# Adafruit_Feather_M0_Basic_rev_C.net
KiCad netlist of a schematic drawn in EAGLE
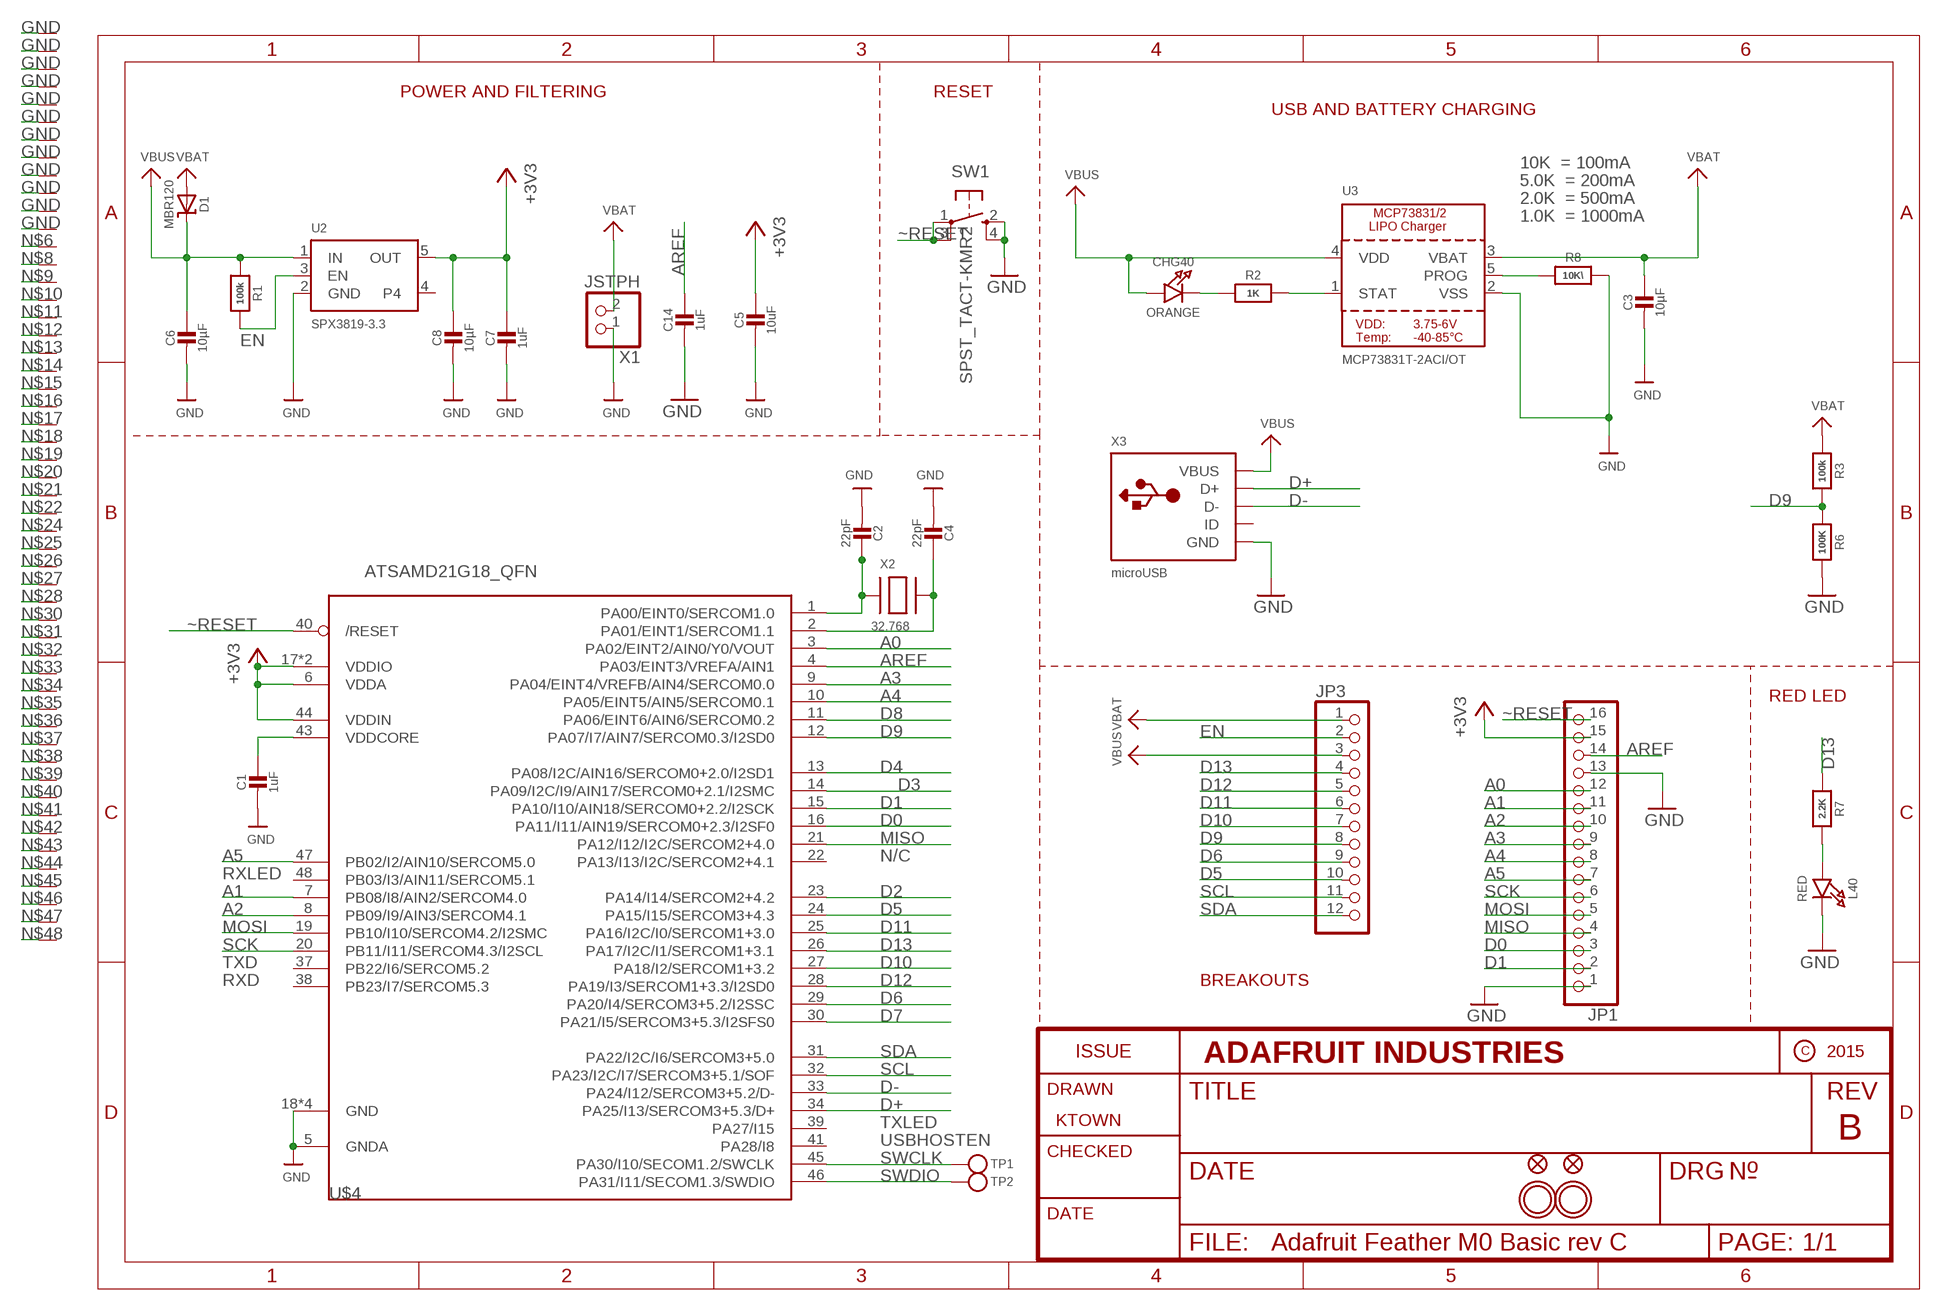
[diagram p0: schematic, sheet 1]

(export (version "E")
  (design (tool "Eeschema 10.0.6"))
  (components
    (comp (ref "C1")
      (value "1uF")
      (footprint "eagle-import:0603-NO")
      (libsource (lib "eagle-import") (part "CAP_CERAMIC0603_NO"))
    )
    (comp (ref "C2")
      (value "22pF")
      (footprint "eagle-import:0603-NO")
      (libsource (lib "eagle-import") (part "CAP_CERAMIC0603_NO"))
    )
    (comp (ref "C3")
      (value "10µF")
      (footprint "eagle-import:0805-NO")
      (libsource (lib "eagle-import") (part "CAP_CERAMIC0805-NOOUTLINE"))
    )
    (comp (ref "C4")
      (value "22pF")
      (footprint "eagle-import:0603-NO")
      (libsource (lib "eagle-import") (part "CAP_CERAMIC0603_NO"))
    )
    (comp (ref "C5")
      (value "10uF")
      (footprint "eagle-import:0805-NO")
      (libsource (lib "eagle-import") (part "CAP_CERAMIC0805-NOOUTLINE"))
    )
    (comp (ref "C6")
      (value "10µF")
      (footprint "eagle-import:0805-NO")
      (libsource (lib "eagle-import") (part "CAP_CERAMIC0805-NOOUTLINE"))
    )
    (comp (ref "C7")
      (value "1uF")
      (footprint "eagle-import:0603-NO")
      (libsource (lib "eagle-import") (part "CAP_CERAMIC0603_NO"))
    )
    (comp (ref "C8")
      (value "10µF")
      (footprint "eagle-import:0805-NO")
      (libsource (lib "eagle-import") (part "CAP_CERAMIC0805-NOOUTLINE"))
    )
    (comp (ref "C14")
      (value "1uF")
      (footprint "eagle-import:0603-NO")
      (libsource (lib "eagle-import") (part "CAP_CERAMIC0603_NO"))
    )
    (comp (ref "CHG40")
      (value "ORANGE")
      (footprint "eagle-import:CHIPLED_0805_NOOUTLINE")
      (libsource (lib "eagle-import") (part "LED0805_NOOUTLINE"))
    )
    (comp (ref "D1")
      (value "MBR120")
      (footprint "eagle-import:SOD-123")
      (libsource (lib "eagle-import") (part "DIODE-SCHOTTKYSOD-123"))
    )
    (comp (ref "JP1")
      (value "HEADER-1X16ROUND")
      (footprint "eagle-import:1X16_ROUND")
      (libsource (lib "eagle-import") (part "HEADER-1X16ROUND"))
    )
    (comp (ref "JP3")
      (value "HEADER-1X12")
      (footprint "eagle-import:1X12_ROUND")
      (libsource (lib "eagle-import") (part "HEADER-1X12"))
    )
    (comp (ref "L40")
      (value "RED")
      (footprint "eagle-import:CHIPLED_0805_NOOUTLINE")
      (libsource (lib "eagle-import") (part "LED0805_NOOUTLINE"))
    )
    (comp (ref "R1")
      (value "100k")
      (footprint "eagle-import:0603-NO")
      (libsource (lib "eagle-import") (part "RESISTOR_0603_NOOUT"))
    )
    (comp (ref "R2")
      (value "1K")
      (footprint "eagle-import:0603-NO")
      (libsource (lib "eagle-import") (part "RESISTOR_0603_NOOUT"))
    )
    (comp (ref "R3")
      (value "100k")
      (footprint "eagle-import:0603-NO")
      (libsource (lib "eagle-import") (part "RESISTOR_0603_NOOUT"))
    )
    (comp (ref "R6")
      (value "100K")
      (footprint "eagle-import:0603-NO")
      (libsource (lib "eagle-import") (part "RESISTOR_0603_NOOUT"))
    )
    (comp (ref "R7")
      (value "2.2K")
      (footprint "eagle-import:0603-NO")
      (libsource (lib "eagle-import") (part "RESISTOR_0603_NOOUT"))
    )
    (comp (ref "R8")
      (value "10K\\")
      (footprint "eagle-import:0603-NO")
      (libsource (lib "eagle-import") (part "RESISTOR_0603_NOOUT"))
    )
    (comp (ref "SW1")
      (value "SPST_TACT-KMR2")
      (footprint "eagle-import:KMR2")
      (libsource (lib "eagle-import") (part "SPST_TACT-KMR2"))
    )
    (comp (ref "TP1")
      (value "TESTPOINTROUND1.5MM")
      (footprint "eagle-import:TESTPOINT_ROUND_1.5MM")
      (libsource (lib "eagle-import") (part "TESTPOINTROUND1.5MM"))
    )
    (comp (ref "TP2")
      (value "TESTPOINTROUND1.5MM")
      (footprint "eagle-import:TESTPOINT_ROUND_1.5MM")
      (libsource (lib "eagle-import") (part "TESTPOINTROUND1.5MM"))
    )
    (comp (ref "U$4")
      (value "ATSAMD21G18_QFN")
      (footprint "eagle-import:TQFN48_7MM")
      (libsource (lib "eagle-import") (part "ATSAMD21J_QFN"))
    )
    (comp (ref "U$31")
      (value "MOUNTINGHOLE2.5")
      (footprint "eagle-import:MOUNTINGHOLE_2.5_PLATED")
      (libsource (lib "eagle-import") (part "MOUNTINGHOLE2.5"))
    )
    (comp (ref "U$32")
      (value "MOUNTINGHOLE2.5")
      (footprint "eagle-import:MOUNTINGHOLE_2.5_PLATED")
      (libsource (lib "eagle-import") (part "MOUNTINGHOLE2.5"))
    )
    (comp (ref "U$34")
      (value "FIDUCIAL\"\"")
      (footprint "eagle-import:FIDUCIAL_1MM")
      (libsource (lib "eagle-import") (part "FIDUCIAL{dblquote}{dblquote}"))
    )
    (comp (ref "U$35")
      (value "FIDUCIAL\"\"")
      (footprint "eagle-import:FIDUCIAL_1MM")
      (libsource (lib "eagle-import") (part "FIDUCIAL{dblquote}{dblquote}"))
    )
    (comp (ref "U2")
      (value "SPX3819-3.3")
      (footprint "eagle-import:SOT23-5")
      (libsource (lib "eagle-import") (part "VREG_SOT23-5"))
    )
    (comp (ref "U3")
      (value "MCP73831T-2ACI/OT")
      (footprint "eagle-import:SOT23-5")
      (libsource (lib "eagle-import") (part "MCP73831/2"))
    )
    (comp (ref "VP_0")
      (value "VPDEV0")
      (footprint "eagle-import:VPAC0")
      (libsource (lib "eagle-import") (part "VPDEV0"))
    )
    (comp (ref "VP_1")
      (value "VPDEV0")
      (footprint "eagle-import:VPAC0")
      (libsource (lib "eagle-import") (part "VPDEV0"))
    )
    (comp (ref "VP_2")
      (value "VPDEV0")
      (footprint "eagle-import:VPAC0")
      (libsource (lib "eagle-import") (part "VPDEV0"))
    )
    (comp (ref "VP_3")
      (value "VPDEV0")
      (footprint "eagle-import:VPAC0")
      (libsource (lib "eagle-import") (part "VPDEV0"))
    )
    (comp (ref "VP_4")
      (value "VPDEV0")
      (footprint "eagle-import:VPAC0")
      (libsource (lib "eagle-import") (part "VPDEV0"))
    )
    (comp (ref "VP_5")
      (value "VPDEV0")
      (footprint "eagle-import:VPAC0")
      (libsource (lib "eagle-import") (part "VPDEV0"))
    )
    (comp (ref "VP_6")
      (value "VPDEV0")
      (footprint "eagle-import:VPAC0")
      (libsource (lib "eagle-import") (part "VPDEV0"))
    )
    (comp (ref "VP_7")
      (value "VPDEV0")
      (footprint "eagle-import:VPAC0")
      (libsource (lib "eagle-import") (part "VPDEV0"))
    )
    (comp (ref "VP_8")
      (value "VPDEV0")
      (footprint "eagle-import:VPAC0")
      (libsource (lib "eagle-import") (part "VPDEV0"))
    )
    (comp (ref "VP_9")
      (value "VPDEV0")
      (footprint "eagle-import:VPAC0")
      (libsource (lib "eagle-import") (part "VPDEV0"))
    )
    (comp (ref "VP_10")
      (value "VPDEV0")
      (footprint "eagle-import:VPAC0")
      (libsource (lib "eagle-import") (part "VPDEV0"))
    )
    (comp (ref "VP_11")
      (value "VPDEV0")
      (footprint "eagle-import:VPAC0")
      (libsource (lib "eagle-import") (part "VPDEV0"))
    )
    (comp (ref "VP_12")
      (value "VPDEV1")
      (footprint "eagle-import:VPAC1")
      (libsource (lib "eagle-import") (part "VPDEV1"))
    )
    (comp (ref "VP_13")
      (value "VPDEV1")
      (footprint "eagle-import:VPAC1")
      (libsource (lib "eagle-import") (part "VPDEV1"))
    )
    (comp (ref "VP_14")
      (value "VPDEV1")
      (footprint "eagle-import:VPAC1")
      (libsource (lib "eagle-import") (part "VPDEV1"))
    )
    (comp (ref "VP_15")
      (value "VPDEV1")
      (footprint "eagle-import:VPAC1")
      (libsource (lib "eagle-import") (part "VPDEV1"))
    )
    (comp (ref "VP_16")
      (value "VPDEV1")
      (footprint "eagle-import:VPAC1")
      (libsource (lib "eagle-import") (part "VPDEV1"))
    )
    (comp (ref "VP_17")
      (value "VPDEV1")
      (footprint "eagle-import:VPAC1")
      (libsource (lib "eagle-import") (part "VPDEV1"))
    )
    (comp (ref "VP_18")
      (value "VPDEV1")
      (footprint "eagle-import:VPAC1")
      (libsource (lib "eagle-import") (part "VPDEV1"))
    )
    (comp (ref "VP_19")
      (value "VPDEV1")
      (footprint "eagle-import:VPAC1")
      (libsource (lib "eagle-import") (part "VPDEV1"))
    )
    (comp (ref "VP_20")
      (value "VPDEV1")
      (footprint "eagle-import:VPAC1")
      (libsource (lib "eagle-import") (part "VPDEV1"))
    )
    (comp (ref "VP_21")
      (value "VPDEV1")
      (footprint "eagle-import:VPAC1")
      (libsource (lib "eagle-import") (part "VPDEV1"))
    )
    (comp (ref "VP_22")
      (value "VPDEV1")
      (footprint "eagle-import:VPAC1")
      (libsource (lib "eagle-import") (part "VPDEV1"))
    )
    (comp (ref "VP_23")
      (value "VPDEV1")
      (footprint "eagle-import:VPAC1")
      (libsource (lib "eagle-import") (part "VPDEV1"))
    )
    (comp (ref "VP_24")
      (value "VPDEV1")
      (footprint "eagle-import:VPAC1")
      (libsource (lib "eagle-import") (part "VPDEV1"))
    )
    (comp (ref "VP_25")
      (value "VPDEV1")
      (footprint "eagle-import:VPAC1")
      (libsource (lib "eagle-import") (part "VPDEV1"))
    )
    (comp (ref "VP_26")
      (value "VPDEV1")
      (footprint "eagle-import:VPAC1")
      (libsource (lib "eagle-import") (part "VPDEV1"))
    )
    (comp (ref "VP_27")
      (value "VPDEV1")
      (footprint "eagle-import:VPAC1")
      (libsource (lib "eagle-import") (part "VPDEV1"))
    )
    (comp (ref "VP_28")
      (value "VPDEV1")
      (footprint "eagle-import:VPAC1")
      (libsource (lib "eagle-import") (part "VPDEV1"))
    )
    (comp (ref "VP_29")
      (value "VPDEV1")
      (footprint "eagle-import:VPAC1")
      (libsource (lib "eagle-import") (part "VPDEV1"))
    )
    (comp (ref "VP_30")
      (value "VPDEV1")
      (footprint "eagle-import:VPAC1")
      (libsource (lib "eagle-import") (part "VPDEV1"))
    )
    (comp (ref "VP_31")
      (value "VPDEV1")
      (footprint "eagle-import:VPAC1")
      (libsource (lib "eagle-import") (part "VPDEV1"))
    )
    (comp (ref "VP_32")
      (value "VPDEV1")
      (footprint "eagle-import:VPAC1")
      (libsource (lib "eagle-import") (part "VPDEV1"))
    )
    (comp (ref "VP_33")
      (value "VPDEV1")
      (footprint "eagle-import:VPAC1")
      (libsource (lib "eagle-import") (part "VPDEV1"))
    )
    (comp (ref "VP_34")
      (value "VPDEV1")
      (footprint "eagle-import:VPAC1")
      (libsource (lib "eagle-import") (part "VPDEV1"))
    )
    (comp (ref "VP_35")
      (value "VPDEV1")
      (footprint "eagle-import:VPAC1")
      (libsource (lib "eagle-import") (part "VPDEV1"))
    )
    (comp (ref "VP_36")
      (value "VPDEV1")
      (footprint "eagle-import:VPAC1")
      (libsource (lib "eagle-import") (part "VPDEV1"))
    )
    (comp (ref "VP_37")
      (value "VPDEV1")
      (footprint "eagle-import:VPAC1")
      (libsource (lib "eagle-import") (part "VPDEV1"))
    )
    (comp (ref "VP_38")
      (value "VPDEV1")
      (footprint "eagle-import:VPAC1")
      (libsource (lib "eagle-import") (part "VPDEV1"))
    )
    (comp (ref "VP_39")
      (value "VPDEV1")
      (footprint "eagle-import:VPAC1")
      (libsource (lib "eagle-import") (part "VPDEV1"))
    )
    (comp (ref "VP_40")
      (value "VPDEV1")
      (footprint "eagle-import:VPAC1")
      (libsource (lib "eagle-import") (part "VPDEV1"))
    )
    (comp (ref "VP_41")
      (value "VPDEV1")
      (footprint "eagle-import:VPAC1")
      (libsource (lib "eagle-import") (part "VPDEV1"))
    )
    (comp (ref "VP_42")
      (value "VPDEV1")
      (footprint "eagle-import:VPAC1")
      (libsource (lib "eagle-import") (part "VPDEV1"))
    )
    (comp (ref "VP_43")
      (value "VPDEV1")
      (footprint "eagle-import:VPAC1")
      (libsource (lib "eagle-import") (part "VPDEV1"))
    )
    (comp (ref "VP_44")
      (value "VPDEV1")
      (footprint "eagle-import:VPAC1")
      (libsource (lib "eagle-import") (part "VPDEV1"))
    )
    (comp (ref "VP_45")
      (value "VPDEV1")
      (footprint "eagle-import:VPAC1")
      (libsource (lib "eagle-import") (part "VPDEV1"))
    )
    (comp (ref "VP_46")
      (value "VPDEV1")
      (footprint "eagle-import:VPAC1")
      (libsource (lib "eagle-import") (part "VPDEV1"))
    )
    (comp (ref "VP_47")
      (value "VPDEV1")
      (footprint "eagle-import:VPAC1")
      (libsource (lib "eagle-import") (part "VPDEV1"))
    )
    (comp (ref "VP_48")
      (value "VPDEV1")
      (footprint "eagle-import:VPAC1")
      (libsource (lib "eagle-import") (part "VPDEV1"))
    )
    (comp (ref "VP_49")
      (value "VPDEV1")
      (footprint "eagle-import:VPAC1")
      (libsource (lib "eagle-import") (part "VPDEV1"))
    )
    (comp (ref "VP_50")
      (value "VPDEV1")
      (footprint "eagle-import:VPAC1")
      (libsource (lib "eagle-import") (part "VPDEV1"))
    )
    (comp (ref "VP_51")
      (value "VPDEV1")
      (footprint "eagle-import:VPAC1")
      (libsource (lib "eagle-import") (part "VPDEV1"))
    )
    (comp (ref "X1")
      (value "JSTPH")
      (footprint "eagle-import:JSTPH2")
      (libsource (lib "eagle-import") (part "CON_JST_PH_2PIN"))
    )
    (comp (ref "X2")
      (value "32.768")
      (footprint "eagle-import:XTAL3215")
      (libsource (lib "eagle-import") (part "XTAL-3.2X1.5"))
    )
    (comp (ref "X3")
      (value "microUSB")
      (footprint "eagle-import:4UCONN_20329_V2")
      (libsource (lib "eagle-import") (part "USB_MICRO_20329_V2"))
    )
  )
  (nets
    (net (code "1") (name "+3V3") (class "Default")
      (node (ref "C5") (pin "1") (pinfunction "1_1") (pintype "passive"))
      (node (ref "C7") (pin "1") (pinfunction "1_1") (pintype "passive"))
      (node (ref "C8") (pin "1") (pinfunction "1_1") (pintype "passive"))
      (node (ref "JP1") (pin "15") (pinfunction "15_15") (pintype "passive"))
      (node (ref "U$4") (pin "17") (pinfunction "VDDIO_17") (pintype "power_in"))
      (node (ref "U$4") (pin "36") (pinfunction "VDDIO_36") (pintype "power_in"))
      (node (ref "U$4") (pin "44") (pinfunction "VDDIN_44") (pintype "power_in"))
      (node (ref "U$4") (pin "6") (pinfunction "VDDA_6") (pintype "power_in"))
      (node (ref "U2") (pin "5") (pinfunction "OUT_5") (pintype "power_in"))
    )
    (net (code "2") (name "/A0") (class "Default")
      (node (ref "JP1") (pin "12") (pinfunction "12_12") (pintype "passive"))
      (node (ref "U$4") (pin "3") (pinfunction "PA02/EINT2/AIN0/Y0/VOUT_3") (pintype "bidirectional"))
    )
    (net (code "3") (name "/A1") (class "Default")
      (node (ref "JP1") (pin "11") (pinfunction "11_11") (pintype "passive"))
      (node (ref "U$4") (pin "7") (pinfunction "PB08/I8/AIN2/SERCOM4.0_7") (pintype "bidirectional"))
    )
    (net (code "4") (name "/A2") (class "Default")
      (node (ref "JP1") (pin "10") (pinfunction "10_10") (pintype "passive"))
      (node (ref "U$4") (pin "8") (pinfunction "PB09/I9/AIN3/SERCOM4.1_8") (pintype "bidirectional"))
    )
    (net (code "5") (name "/A3") (class "Default")
      (node (ref "JP1") (pin "9") (pinfunction "9_9") (pintype "passive"))
      (node (ref "U$4") (pin "9") (pinfunction "PA04/EINT4/VREFB/AIN4/SERCOM0.0_9") (pintype "bidirectional"))
    )
    (net (code "6") (name "/A4") (class "Default")
      (node (ref "JP1") (pin "8") (pinfunction "8_8") (pintype "passive"))
      (node (ref "U$4") (pin "10") (pinfunction "PA05/EINT5/AIN5/SERCOM0.1_10") (pintype "bidirectional"))
    )
    (net (code "7") (name "/A5") (class "Default")
      (node (ref "JP1") (pin "7") (pinfunction "7_7") (pintype "passive"))
      (node (ref "U$4") (pin "47") (pinfunction "PB02/I2/AIN10/SERCOM5.0_47") (pintype "bidirectional"))
    )
    (net (code "8") (name "/AREF") (class "Default")
      (node (ref "C14") (pin "1") (pinfunction "1_1") (pintype "passive"))
      (node (ref "JP1") (pin "14") (pinfunction "14_14") (pintype "passive"))
      (node (ref "U$4") (pin "4") (pinfunction "PA03/EINT3/VREFA/AIN1_4") (pintype "bidirectional"))
    )
    (net (code "9") (name "/D+") (class "Default")
      (node (ref "U$4") (pin "34") (pinfunction "PA25/I13/SERCOM3+5.3/D+_34") (pintype "bidirectional"))
      (node (ref "X3") (pin "D+") (pinfunction "D+_D+") (pintype "bidirectional"))
    )
    (net (code "10") (name "/D-") (class "Default")
      (node (ref "U$4") (pin "33") (pinfunction "PA24/I12/SERCOM3+5.2/D-_33") (pintype "bidirectional"))
      (node (ref "X3") (pin "D-") (pinfunction "D-_D-") (pintype "bidirectional"))
    )
    (net (code "11") (name "/D0") (class "Default")
      (node (ref "JP1") (pin "3") (pinfunction "3_3") (pintype "passive"))
      (node (ref "U$4") (pin "16") (pinfunction "PA11/I11/AIN19/SERCOM0+2.3/I2SF0_16") (pintype "bidirectional"))
    )
    (net (code "12") (name "/D1") (class "Default")
      (node (ref "JP1") (pin "2") (pinfunction "2_2") (pintype "passive"))
      (node (ref "U$4") (pin "15") (pinfunction "PA10/I10/AIN18/SERCOM0+2.2/I2SCK_15") (pintype "bidirectional"))
    )
    (net (code "13") (name "/D2") (class "Default")
      (node (ref "U$4") (pin "23") (pinfunction "PA14/I14/SERCOM2+4.2_23") (pintype "bidirectional"))
    )
    (net (code "14") (name "/D3") (class "Default")
      (node (ref "U$4") (pin "14") (pinfunction "PA09/I2C/I9/AIN17/SERCOM0+2.1/I2SMC_14") (pintype "bidirectional"))
    )
    (net (code "15") (name "/D4") (class "Default")
      (node (ref "U$4") (pin "13") (pinfunction "PA08/I2C/AIN16/SERCOM0+2.0/I2SD1_13") (pintype "bidirectional"))
    )
    (net (code "16") (name "/D5") (class "Default")
      (node (ref "JP3") (pin "10") (pinfunction "10_10") (pintype "passive"))
      (node (ref "U$4") (pin "24") (pinfunction "PA15/I15/SERCOM3+4.3_24") (pintype "bidirectional"))
    )
    (net (code "17") (name "/D6") (class "Default")
      (node (ref "JP3") (pin "9") (pinfunction "9_9") (pintype "passive"))
      (node (ref "U$4") (pin "29") (pinfunction "PA20/I4/SERCOM3+5.2/I2SSC_29") (pintype "bidirectional"))
    )
    (net (code "18") (name "/D7") (class "Default")
      (node (ref "U$4") (pin "30") (pinfunction "PA21/I5/SERCOM3+5.3/I2SFS0_30") (pintype "bidirectional"))
    )
    (net (code "19") (name "/D8") (class "Default")
      (node (ref "U$4") (pin "11") (pinfunction "PA06/EINT6/AIN6/SERCOM0.2_11") (pintype "bidirectional"))
    )
    (net (code "20") (name "/D9") (class "Default")
      (node (ref "JP3") (pin "8") (pinfunction "8_8") (pintype "passive"))
      (node (ref "R3") (pin "2") (pinfunction "2_2") (pintype "passive"))
      (node (ref "R6") (pin "1") (pinfunction "1_1") (pintype "passive"))
      (node (ref "U$4") (pin "12") (pinfunction "PA07/I7/AIN7/SERCOM0.3/I2SD0_12") (pintype "bidirectional"))
    )
    (net (code "21") (name "/D10") (class "Default")
      (node (ref "JP3") (pin "7") (pinfunction "7_7") (pintype "passive"))
      (node (ref "U$4") (pin "27") (pinfunction "PA18/I2/SERCOM1+3.2_27") (pintype "bidirectional"))
    )
    (net (code "22") (name "/D11") (class "Default")
      (node (ref "JP3") (pin "6") (pinfunction "6_6") (pintype "passive"))
      (node (ref "U$4") (pin "25") (pinfunction "PA16/I2C/I0/SERCOM1+3.0_25") (pintype "bidirectional"))
    )
    (net (code "23") (name "/D12") (class "Default")
      (node (ref "JP3") (pin "5") (pinfunction "5_5") (pintype "passive"))
      (node (ref "U$4") (pin "28") (pinfunction "PA19/I3/SERCOM1+3.3/I2SD0_28") (pintype "bidirectional"))
    )
    (net (code "24") (name "/D13") (class "Default")
      (node (ref "JP3") (pin "4") (pinfunction "4_4") (pintype "passive"))
      (node (ref "R7") (pin "1") (pinfunction "1_1") (pintype "passive"))
      (node (ref "U$4") (pin "26") (pinfunction "PA17/I2C/I1/SERCOM1+3.1_26") (pintype "bidirectional"))
    )
    (net (code "25") (name "/EN") (class "Default")
      (node (ref "JP3") (pin "2") (pinfunction "2_2") (pintype "passive"))
      (node (ref "R1") (pin "2") (pinfunction "2_2") (pintype "passive"))
      (node (ref "U2") (pin "3") (pinfunction "EN_3") (pintype "input"))
    )
    (net (code "26") (name "/MISO") (class "Default")
      (node (ref "JP1") (pin "4") (pinfunction "4_4") (pintype "passive"))
      (node (ref "U$4") (pin "21") (pinfunction "PA12/I12/I2C/SERCOM2+4.0_21") (pintype "bidirectional"))
    )
    (net (code "27") (name "/MOSI") (class "Default")
      (node (ref "JP1") (pin "5") (pinfunction "5_5") (pintype "passive"))
      (node (ref "U$4") (pin "19") (pinfunction "PB10/I10/SERCOM4.2/I2SMC_19") (pintype "bidirectional"))
    )
    (net (code "28") (name "/N$6") (class "Default")
      (node (ref "VP_12") (pin "VP") (pinfunction "VP_VP") (pintype "passive"))
    )
    (net (code "29") (name "/N$8") (class "Default")
      (node (ref "VP_13") (pin "VP") (pinfunction "VP_VP") (pintype "passive"))
    )
    (net (code "30") (name "/N$9") (class "Default")
      (node (ref "VP_14") (pin "VP") (pinfunction "VP_VP") (pintype "passive"))
    )
    (net (code "31") (name "/N$10") (class "Default")
      (node (ref "VP_15") (pin "VP") (pinfunction "VP_VP") (pintype "passive"))
    )
    (net (code "32") (name "/N$11") (class "Default")
      (node (ref "VP_16") (pin "VP") (pinfunction "VP_VP") (pintype "passive"))
    )
    (net (code "33") (name "/N$12") (class "Default")
      (node (ref "VP_17") (pin "VP") (pinfunction "VP_VP") (pintype "passive"))
    )
    (net (code "34") (name "/N$13") (class "Default")
      (node (ref "VP_18") (pin "VP") (pinfunction "VP_VP") (pintype "passive"))
    )
    (net (code "35") (name "/N$14") (class "Default")
      (node (ref "VP_19") (pin "VP") (pinfunction "VP_VP") (pintype "passive"))
    )
    (net (code "36") (name "/N$15") (class "Default")
      (node (ref "VP_20") (pin "VP") (pinfunction "VP_VP") (pintype "passive"))
    )
    (net (code "37") (name "/N$16") (class "Default")
      (node (ref "VP_21") (pin "VP") (pinfunction "VP_VP") (pintype "passive"))
    )
    (net (code "38") (name "/N$17") (class "Default")
      (node (ref "VP_22") (pin "VP") (pinfunction "VP_VP") (pintype "passive"))
    )
    (net (code "39") (name "/N$18") (class "Default")
      (node (ref "VP_23") (pin "VP") (pinfunction "VP_VP") (pintype "passive"))
    )
    (net (code "40") (name "/N$19") (class "Default")
      (node (ref "VP_24") (pin "VP") (pinfunction "VP_VP") (pintype "passive"))
    )
    (net (code "41") (name "/N$20") (class "Default")
      (node (ref "VP_25") (pin "VP") (pinfunction "VP_VP") (pintype "passive"))
    )
    (net (code "42") (name "/N$21") (class "Default")
      (node (ref "VP_26") (pin "VP") (pinfunction "VP_VP") (pintype "passive"))
    )
    (net (code "43") (name "/N$22") (class "Default")
      (node (ref "VP_27") (pin "VP") (pinfunction "VP_VP") (pintype "passive"))
    )
    (net (code "44") (name "/N$24") (class "Default")
      (node (ref "VP_28") (pin "VP") (pinfunction "VP_VP") (pintype "passive"))
    )
    (net (code "45") (name "/N$25") (class "Default")
      (node (ref "VP_29") (pin "VP") (pinfunction "VP_VP") (pintype "passive"))
    )
    (net (code "46") (name "/N$26") (class "Default")
      (node (ref "VP_30") (pin "VP") (pinfunction "VP_VP") (pintype "passive"))
    )
    (net (code "47") (name "/N$27") (class "Default")
      (node (ref "VP_31") (pin "VP") (pinfunction "VP_VP") (pintype "passive"))
    )
    (net (code "48") (name "/N$28") (class "Default")
      (node (ref "VP_32") (pin "VP") (pinfunction "VP_VP") (pintype "passive"))
    )
    (net (code "49") (name "/N$30") (class "Default")
      (node (ref "VP_33") (pin "VP") (pinfunction "VP_VP") (pintype "passive"))
    )
    (net (code "50") (name "/N$31") (class "Default")
      (node (ref "VP_34") (pin "VP") (pinfunction "VP_VP") (pintype "passive"))
    )
    (net (code "51") (name "/N$32") (class "Default")
      (node (ref "VP_35") (pin "VP") (pinfunction "VP_VP") (pintype "passive"))
    )
    (net (code "52") (name "/N$33") (class "Default")
      (node (ref "VP_36") (pin "VP") (pinfunction "VP_VP") (pintype "passive"))
    )
    (net (code "53") (name "/N$34") (class "Default")
      (node (ref "VP_37") (pin "VP") (pinfunction "VP_VP") (pintype "passive"))
    )
    (net (code "54") (name "/N$35") (class "Default")
      (node (ref "VP_38") (pin "VP") (pinfunction "VP_VP") (pintype "passive"))
    )
    (net (code "55") (name "/N$36") (class "Default")
      (node (ref "VP_39") (pin "VP") (pinfunction "VP_VP") (pintype "passive"))
    )
    (net (code "56") (name "/N$37") (class "Default")
      (node (ref "VP_40") (pin "VP") (pinfunction "VP_VP") (pintype "passive"))
    )
    (net (code "57") (name "/N$38") (class "Default")
      (node (ref "VP_41") (pin "VP") (pinfunction "VP_VP") (pintype "passive"))
    )
    (net (code "58") (name "/N$39") (class "Default")
      (node (ref "VP_42") (pin "VP") (pinfunction "VP_VP") (pintype "passive"))
    )
    (net (code "59") (name "/N$40") (class "Default")
      (node (ref "VP_43") (pin "VP") (pinfunction "VP_VP") (pintype "passive"))
    )
    (net (code "60") (name "/N$41") (class "Default")
      (node (ref "VP_44") (pin "VP") (pinfunction "VP_VP") (pintype "passive"))
    )
    (net (code "61") (name "/N$42") (class "Default")
      (node (ref "VP_45") (pin "VP") (pinfunction "VP_VP") (pintype "passive"))
    )
    (net (code "62") (name "/N$43") (class "Default")
      (node (ref "VP_46") (pin "VP") (pinfunction "VP_VP") (pintype "passive"))
    )
    (net (code "63") (name "/N$44") (class "Default")
      (node (ref "VP_47") (pin "VP") (pinfunction "VP_VP") (pintype "passive"))
    )
    (net (code "64") (name "/N$45") (class "Default")
      (node (ref "VP_48") (pin "VP") (pinfunction "VP_VP") (pintype "passive"))
    )
    (net (code "65") (name "/N$46") (class "Default")
      (node (ref "VP_49") (pin "VP") (pinfunction "VP_VP") (pintype "passive"))
    )
    (net (code "66") (name "/N$47") (class "Default")
      (node (ref "VP_50") (pin "VP") (pinfunction "VP_VP") (pintype "passive"))
    )
    (net (code "67") (name "/N$48") (class "Default")
      (node (ref "VP_51") (pin "VP") (pinfunction "VP_VP") (pintype "passive"))
    )
    (net (code "68") (name "/SCK") (class "Default")
      (node (ref "JP1") (pin "6") (pinfunction "6_6") (pintype "passive"))
      (node (ref "U$4") (pin "20") (pinfunction "PB11/I11/SERCOM4.3/I2SCL_20") (pintype "bidirectional"))
    )
    (net (code "69") (name "/SCL") (class "Default")
      (node (ref "JP3") (pin "11") (pinfunction "11_11") (pintype "passive"))
      (node (ref "U$4") (pin "32") (pinfunction "PA23/I2C/I7/SERCOM3+5.1/SOF_32") (pintype "bidirectional"))
    )
    (net (code "70") (name "/SDA") (class "Default")
      (node (ref "JP3") (pin "12") (pinfunction "12_12") (pintype "passive"))
      (node (ref "U$4") (pin "31") (pinfunction "PA22/I2C/I6/SERCOM3+5.0_31") (pintype "bidirectional"))
    )
    (net (code "71") (name "/SWCLK") (class "Default")
      (node (ref "TP1") (pin "P$1") (pinfunction "P$1_P$1") (pintype "bidirectional"))
      (node (ref "U$4") (pin "45") (pinfunction "PA30/I10/SECOM1.2/SWCLK_45") (pintype "bidirectional"))
    )
    (net (code "72") (name "/SWDIO") (class "Default")
      (node (ref "TP2") (pin "P$1") (pinfunction "P$1_P$1") (pintype "bidirectional"))
      (node (ref "U$4") (pin "46") (pinfunction "PA31/I11/SECOM1.3/SWDIO_46") (pintype "bidirectional"))
    )
    (net (code "73") (name "/~{RESET}") (class "Default")
      (node (ref "JP1") (pin "16") (pinfunction "16_16") (pintype "passive"))
      (node (ref "SW1") (pin "1") (pinfunction "P_1") (pintype "passive"))
      (node (ref "SW1") (pin "3") (pinfunction "P1_3") (pintype "passive"))
      (node (ref "U$4") (pin "40") (pinfunction "/RESET_40") (pintype "bidirectional"))
    )
    (net (code "74") (name "GND") (class "Default")
      (node (ref "C1") (pin "2") (pinfunction "2_2") (pintype "passive"))
      (node (ref "C14") (pin "2") (pinfunction "2_2") (pintype "passive"))
      (node (ref "C2") (pin "2") (pinfunction "2_2") (pintype "passive"))
      (node (ref "C3") (pin "2") (pinfunction "2_2") (pintype "passive"))
      (node (ref "C4") (pin "2") (pinfunction "2_2") (pintype "passive"))
      (node (ref "C5") (pin "2") (pinfunction "2_2") (pintype "passive"))
      (node (ref "C6") (pin "2") (pinfunction "2_2") (pintype "passive"))
      (node (ref "C7") (pin "2") (pinfunction "2_2") (pintype "passive"))
      (node (ref "C8") (pin "2") (pinfunction "2_2") (pintype "passive"))
      (node (ref "JP1") (pin "1") (pinfunction "1_1") (pintype "passive"))
      (node (ref "JP1") (pin "13") (pinfunction "13_13") (pintype "passive"))
      (node (ref "L40") (pin "C") (pinfunction "C_C") (pintype "passive"))
      (node (ref "R6") (pin "2") (pinfunction "2_2") (pintype "passive"))
      (node (ref "R8") (pin "2") (pinfunction "2_2") (pintype "passive"))
      (node (ref "SW1") (pin "2") (pinfunction "S_2") (pintype "passive"))
      (node (ref "SW1") (pin "4") (pinfunction "S1_4") (pintype "passive"))
      (node (ref "U$4") (pin "18") (pinfunction "GND_18") (pintype "power_in"))
      (node (ref "U$4") (pin "35") (pinfunction "GND_35") (pintype "power_in"))
      (node (ref "U$4") (pin "42") (pinfunction "GND_42") (pintype "power_in"))
      (node (ref "U$4") (pin "5") (pinfunction "GNDA_5") (pintype "power_in"))
      (node (ref "U$4") (pin "THERMAL") (pinfunction "GND_THERMAL") (pintype "power_in"))
      (node (ref "U2") (pin "2") (pinfunction "GND_2") (pintype "power_in"))
      (node (ref "U3") (pin "2") (pinfunction "VSS_2") (pintype "power_in"))
      (node (ref "VP_0") (pin "VP") (pinfunction "VP_VP") (pintype "passive"))
      (node (ref "VP_1") (pin "VP") (pinfunction "VP_VP") (pintype "passive"))
      (node (ref "VP_10") (pin "VP") (pinfunction "VP_VP") (pintype "passive"))
      (node (ref "VP_11") (pin "VP") (pinfunction "VP_VP") (pintype "passive"))
      (node (ref "VP_2") (pin "VP") (pinfunction "VP_VP") (pintype "passive"))
      (node (ref "VP_3") (pin "VP") (pinfunction "VP_VP") (pintype "passive"))
      (node (ref "VP_4") (pin "VP") (pinfunction "VP_VP") (pintype "passive"))
      (node (ref "VP_5") (pin "VP") (pinfunction "VP_VP") (pintype "passive"))
      (node (ref "VP_6") (pin "VP") (pinfunction "VP_VP") (pintype "passive"))
      (node (ref "VP_7") (pin "VP") (pinfunction "VP_VP") (pintype "passive"))
      (node (ref "VP_8") (pin "VP") (pinfunction "VP_VP") (pintype "passive"))
      (node (ref "VP_9") (pin "VP") (pinfunction "VP_VP") (pintype "passive"))
      (node (ref "X1") (pin "1") (pinfunction "1_1") (pintype "passive"))
      (node (ref "X3") (pin "BASE@1") (pinfunction "GND_BASE@1") (pintype "power_in"))
      (node (ref "X3") (pin "BASE@2") (pinfunction "GND_BASE@2") (pintype "power_in"))
      (node (ref "X3") (pin "GND") (pinfunction "GND_GND") (pintype "power_in"))
      (node (ref "X3") (pin "SPRT@1") (pinfunction "GND_SPRT@1") (pintype "power_in"))
      (node (ref "X3") (pin "SPRT@2") (pinfunction "GND_SPRT@2") (pintype "power_in"))
      (node (ref "X3") (pin "SPRT@3") (pinfunction "GND_SPRT@3") (pintype "power_in"))
      (node (ref "X3") (pin "SPRT@4") (pinfunction "GND_SPRT@4") (pintype "power_in"))
    )
    (net (code "75") (name "Net-(CHG40-PadC)") (class "Default")
      (node (ref "CHG40") (pin "C") (pinfunction "C_C") (pintype "passive"))
      (node (ref "R2") (pin "1") (pinfunction "1_1") (pintype "passive"))
    )
    (net (code "76") (name "Net-(L40-PadA)") (class "Default")
      (node (ref "L40") (pin "A") (pinfunction "A_A") (pintype "passive"))
      (node (ref "R7") (pin "2") (pinfunction "2_2") (pintype "passive"))
    )
    (net (code "77") (name "Net-(U$4-PA00{slash}EINT0{slash}SERCOM1.0)") (class "Default")
      (node (ref "C2") (pin "1") (pinfunction "1_1") (pintype "passive"))
      (node (ref "U$4") (pin "1") (pinfunction "PA00/EINT0/SERCOM1.0_1") (pintype "bidirectional"))
      (node (ref "X2") (pin "P$1") (pinfunction "P$1_P$1") (pintype "bidirectional"))
    )
    (net (code "78") (name "Net-(U$4-PA01{slash}EINT1{slash}SERCOM1.1)") (class "Default")
      (node (ref "C4") (pin "1") (pinfunction "1_1") (pintype "passive"))
      (node (ref "U$4") (pin "2") (pinfunction "PA01/EINT1/SERCOM1.1_2") (pintype "bidirectional"))
      (node (ref "X2") (pin "P$2") (pinfunction "P$2_P$2") (pintype "bidirectional"))
    )
    (net (code "79") (name "Net-(U$4-VDDCORE)") (class "Default")
      (node (ref "C1") (pin "1") (pinfunction "1_1") (pintype "passive"))
      (node (ref "U$4") (pin "43") (pinfunction "VDDCORE_43") (pintype "power_in"))
    )
    (net (code "80") (name "Net-(U3-PROG)") (class "Default")
      (node (ref "R8") (pin "1") (pinfunction "1_1") (pintype "passive"))
      (node (ref "U3") (pin "5") (pinfunction "PROG_5") (pintype "input"))
    )
    (net (code "81") (name "Net-(U3-STAT)") (class "Default")
      (node (ref "R2") (pin "2") (pinfunction "2_2") (pintype "passive"))
      (node (ref "U3") (pin "1") (pinfunction "STAT_1") (pintype "output"))
    )
    (net (code "82") (name "VBAT") (class "Default")
      (node (ref "C3") (pin "1") (pinfunction "1_1") (pintype "passive"))
      (node (ref "D1") (pin "A") (pinfunction "A_A") (pintype "passive"))
      (node (ref "JP3") (pin "1") (pinfunction "1_1") (pintype "passive"))
      (node (ref "R3") (pin "1") (pinfunction "1_1") (pintype "passive"))
      (node (ref "U3") (pin "3") (pinfunction "VBAT_3") (pintype "power_in"))
      (node (ref "X1") (pin "2") (pinfunction "2_2") (pintype "passive"))
    )
    (net (code "83") (name "VBUS") (class "Default")
      (node (ref "C6") (pin "1") (pinfunction "1_1") (pintype "passive"))
      (node (ref "CHG40") (pin "A") (pinfunction "A_A") (pintype "passive"))
      (node (ref "D1") (pin "C") (pinfunction "C_C") (pintype "passive"))
      (node (ref "JP3") (pin "3") (pinfunction "3_3") (pintype "passive"))
      (node (ref "R1") (pin "1") (pinfunction "1_1") (pintype "passive"))
      (node (ref "U2") (pin "1") (pinfunction "IN_1") (pintype "power_in"))
      (node (ref "U3") (pin "4") (pinfunction "VDD_4") (pintype "power_in"))
      (node (ref "X3") (pin "VBUS") (pinfunction "VBUS_VBUS") (pintype "power_in"))
    )
    (net (code "84") (name "unconnected-(U$4-PA13{slash}I13{slash}I2C{slash}SERCOM2+4.1-Pad22)") (class "Default")
      (node (ref "U$4") (pin "22") (pinfunction "PA13/I13/I2C/SERCOM2+4.1_22") (pintype "bidirectional"))
    )
    (net (code "85") (name "unconnected-(U$4-PA27{slash}I15-Pad39)") (class "Default")
      (node (ref "U$4") (pin "39") (pinfunction "PA27/I15_39") (pintype "bidirectional"))
    )
    (net (code "86") (name "unconnected-(U$4-PA28{slash}I8-Pad41)") (class "Default")
      (node (ref "U$4") (pin "41") (pinfunction "PA28/I8_41") (pintype "bidirectional"))
    )
    (net (code "87") (name "unconnected-(U$4-PB03{slash}I3{slash}AIN11{slash}SERCOM5.1-Pad48)") (class "Default")
      (node (ref "U$4") (pin "48") (pinfunction "PB03/I3/AIN11/SERCOM5.1_48") (pintype "bidirectional"))
    )
    (net (code "88") (name "unconnected-(U$4-PB22{slash}I6{slash}SERCOM5.2-Pad37)") (class "Default")
      (node (ref "U$4") (pin "37") (pinfunction "PB22/I6/SERCOM5.2_37") (pintype "bidirectional"))
    )
    (net (code "89") (name "unconnected-(U$4-PB23{slash}I7{slash}SERCOM5.3-Pad38)") (class "Default")
      (node (ref "U$4") (pin "38") (pinfunction "PB23/I7/SERCOM5.3_38") (pintype "bidirectional"))
    )
    (net (code "90") (name "unconnected-(U2-P4-Pad4)") (class "Default")
      (node (ref "U2") (pin "4") (pinfunction "P4_4") (pintype "bidirectional"))
    )
    (net (code "91") (name "unconnected-(X3-PadID)") (class "Default")
      (node (ref "X3") (pin "ID") (pinfunction "ID_ID") (pintype "bidirectional"))
    )
  )
)
